# 04_SHIELD_SLOT_B.net
KiCad netlist of a schematic drawn in Altium Designer
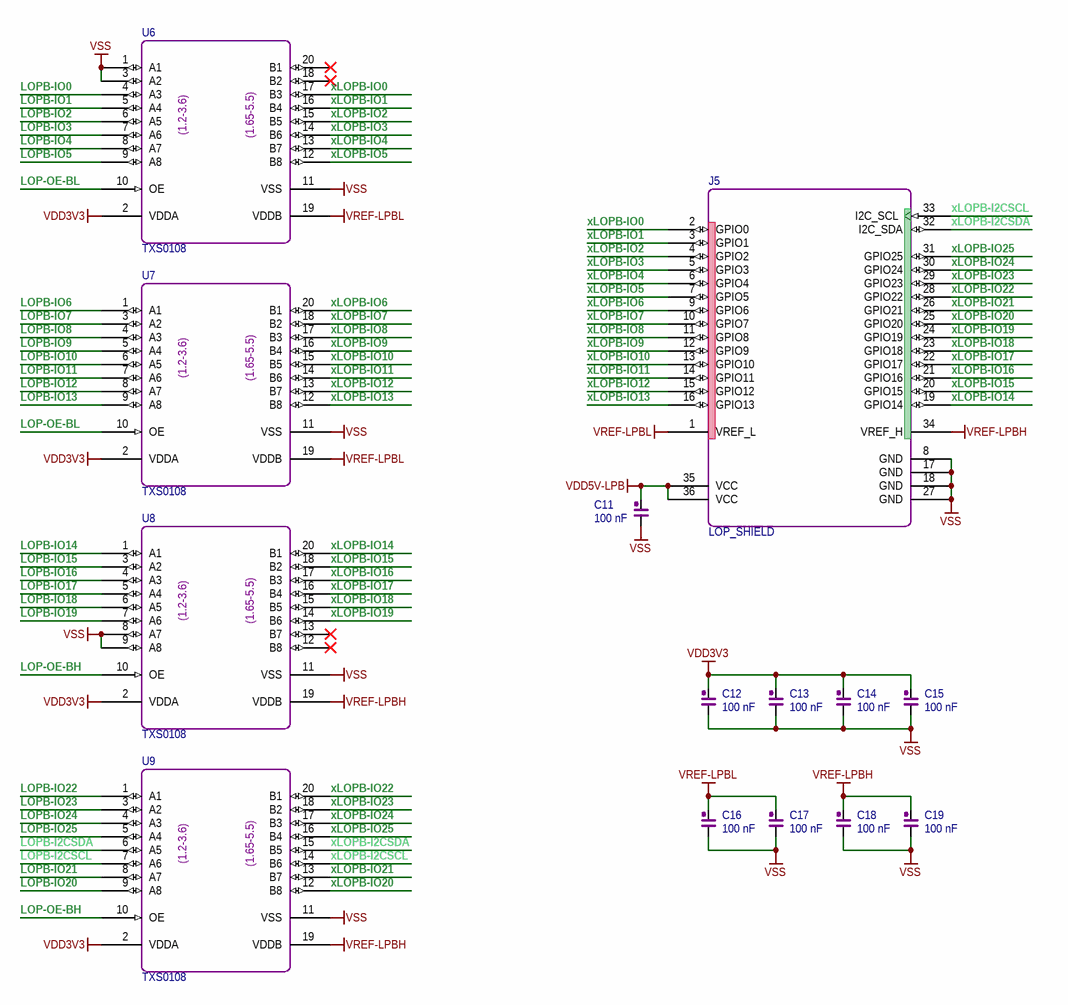
[diagram p0: 04_SHIELD_SLOT_B.SchDoc]

(export (version "E")
  (design (tool "Eeschema 10.0.6"))
  (components
    (comp (ref "C11")
      (value "100 nF")
      (footprint "0603A1")
      (description "Normal Capacitor")
      (fields
        (field (name "PARTNUMBER") "0")
        (field (name "PUBLISHER") "Cowin")
        (field (name "DESIGNER") "shyul")
      )
      (libsource (lib "Basc_1_Passive") (part "CAP"))
    )
    (comp (ref "C12")
      (value "100 nF")
      (footprint "0603A1")
      (description "Normal Capacitor")
      (fields
        (field (name "PARTNUMBER") "0")
        (field (name "PUBLISHER") "Cowin")
        (field (name "DESIGNER") "shyul")
      )
      (libsource (lib "Basc_1_Passive") (part "CAP"))
    )
    (comp (ref "C13")
      (value "100 nF")
      (footprint "0603A1")
      (description "Normal Capacitor")
      (fields
        (field (name "PARTNUMBER") "0")
        (field (name "PUBLISHER") "Cowin")
        (field (name "DESIGNER") "shyul")
      )
      (libsource (lib "Basc_1_Passive") (part "CAP"))
    )
    (comp (ref "C14")
      (value "100 nF")
      (footprint "0603A1")
      (description "Normal Capacitor")
      (fields
        (field (name "PARTNUMBER") "0")
        (field (name "PUBLISHER") "Cowin")
        (field (name "DESIGNER") "shyul")
      )
      (libsource (lib "Basc_1_Passive") (part "CAP"))
    )
    (comp (ref "C15")
      (value "100 nF")
      (footprint "0603A1")
      (description "Normal Capacitor")
      (fields
        (field (name "PARTNUMBER") "0")
        (field (name "PUBLISHER") "Cowin")
        (field (name "DESIGNER") "shyul")
      )
      (libsource (lib "Basc_1_Passive") (part "CAP"))
    )
    (comp (ref "C16")
      (value "100 nF")
      (footprint "0603A1")
      (description "Normal Capacitor")
      (fields
        (field (name "PARTNUMBER") "0")
        (field (name "PUBLISHER") "Cowin")
        (field (name "DESIGNER") "shyul")
      )
      (libsource (lib "Basc_1_Passive") (part "CAP"))
    )
    (comp (ref "C17")
      (value "100 nF")
      (footprint "0603A1")
      (description "Normal Capacitor")
      (fields
        (field (name "PARTNUMBER") "0")
        (field (name "PUBLISHER") "Cowin")
        (field (name "DESIGNER") "shyul")
      )
      (libsource (lib "Basc_1_Passive") (part "CAP"))
    )
    (comp (ref "C18")
      (value "100 nF")
      (footprint "0603A1")
      (description "Normal Capacitor")
      (fields
        (field (name "PARTNUMBER") "0")
        (field (name "PUBLISHER") "Cowin")
        (field (name "DESIGNER") "shyul")
      )
      (libsource (lib "Basc_1_Passive") (part "CAP"))
    )
    (comp (ref "C19")
      (value "100 nF")
      (footprint "0603A1")
      (description "Normal Capacitor")
      (fields
        (field (name "PARTNUMBER") "0")
        (field (name "PUBLISHER") "Cowin")
        (field (name "DESIGNER") "shyul")
      )
      (libsource (lib "Basc_1_Passive") (part "CAP"))
    )
    (comp (ref "J5")
      (value "LOP_SHIELD")
      (footprint "LOP_SHIELD")
      (description "Lophilo Shield Module Slot")
      (fields (field (name "PUBLISHER") "Cowin") (field (name "DESIGNER") "shyul"))
      (libsource (lib "PCB_LDB-U01") (part "LOP_SHIELD"))
    )
    (comp (ref "U6")
      (value "TXS0108")
      (footprint "TSSOP-20")
      (description "8-bit Translator")
      (fields (field (name "DESIGNER") "shyul") (field (name "PUBLISHER") "Cowin"))
      (libsource (lib "IC_01_Logic") (part "TXS0108"))
    )
    (comp (ref "U7")
      (value "TXS0108")
      (footprint "TSSOP-20")
      (description "8-bit Translator")
      (fields (field (name "DESIGNER") "shyul") (field (name "PUBLISHER") "Cowin"))
      (libsource (lib "IC_01_Logic") (part "TXS0108"))
    )
    (comp (ref "U8")
      (value "TXS0108")
      (footprint "TSSOP-20")
      (description "8-bit Translator")
      (fields (field (name "DESIGNER") "shyul") (field (name "PUBLISHER") "Cowin"))
      (libsource (lib "IC_01_Logic") (part "TXS0108"))
    )
    (comp (ref "U9")
      (value "TXS0108")
      (footprint "TSSOP-20")
      (description "8-bit Translator")
      (fields (field (name "DESIGNER") "shyul") (field (name "PUBLISHER") "Cowin"))
      (libsource (lib "IC_01_Logic") (part "TXS0108"))
    )
  )
  (nets
    (net (code "1") (name "/LOP-OE-BH") (class "Default")
      (node (ref "U8") (pin "10") (pinfunction "OE_10") (pintype "input"))
      (node (ref "U9") (pin "10") (pinfunction "OE_10") (pintype "input"))
    )
    (net (code "2") (name "/LOP-OE-BL") (class "Default")
      (node (ref "U6") (pin "10") (pinfunction "OE_10") (pintype "input"))
      (node (ref "U7") (pin "10") (pinfunction "OE_10") (pintype "input"))
    )
    (net (code "3") (name "/LOPB-I2CSCL") (class "Default")
      (node (ref "U9") (pin "7") (pinfunction "A6_7") (pintype "bidirectional"))
    )
    (net (code "4") (name "/LOPB-I2CSDA") (class "Default")
      (node (ref "U9") (pin "6") (pinfunction "A5_6") (pintype "bidirectional"))
    )
    (net (code "5") (name "/LOPB-IO0") (class "Default")
      (node (ref "U6") (pin "4") (pinfunction "A3_4") (pintype "bidirectional"))
    )
    (net (code "6") (name "/LOPB-IO1") (class "Default")
      (node (ref "U6") (pin "5") (pinfunction "A4_5") (pintype "bidirectional"))
    )
    (net (code "7") (name "/LOPB-IO2") (class "Default")
      (node (ref "U6") (pin "6") (pinfunction "A5_6") (pintype "bidirectional"))
    )
    (net (code "8") (name "/LOPB-IO3") (class "Default")
      (node (ref "U6") (pin "7") (pinfunction "A6_7") (pintype "bidirectional"))
    )
    (net (code "9") (name "/LOPB-IO4") (class "Default")
      (node (ref "U6") (pin "8") (pinfunction "A7_8") (pintype "bidirectional"))
    )
    (net (code "10") (name "/LOPB-IO5") (class "Default")
      (node (ref "U6") (pin "9") (pinfunction "A8_9") (pintype "bidirectional"))
    )
    (net (code "11") (name "/LOPB-IO6") (class "Default")
      (node (ref "U7") (pin "1") (pinfunction "A1_1") (pintype "bidirectional"))
    )
    (net (code "12") (name "/LOPB-IO7") (class "Default")
      (node (ref "U7") (pin "3") (pinfunction "A2_3") (pintype "bidirectional"))
    )
    (net (code "13") (name "/LOPB-IO8") (class "Default")
      (node (ref "U7") (pin "4") (pinfunction "A3_4") (pintype "bidirectional"))
    )
    (net (code "14") (name "/LOPB-IO9") (class "Default")
      (node (ref "U7") (pin "5") (pinfunction "A4_5") (pintype "bidirectional"))
    )
    (net (code "15") (name "/LOPB-IO10") (class "Default")
      (node (ref "U7") (pin "6") (pinfunction "A5_6") (pintype "bidirectional"))
    )
    (net (code "16") (name "/LOPB-IO11") (class "Default")
      (node (ref "U7") (pin "7") (pinfunction "A6_7") (pintype "bidirectional"))
    )
    (net (code "17") (name "/LOPB-IO12") (class "Default")
      (node (ref "U7") (pin "8") (pinfunction "A7_8") (pintype "bidirectional"))
    )
    (net (code "18") (name "/LOPB-IO13") (class "Default")
      (node (ref "U7") (pin "9") (pinfunction "A8_9") (pintype "bidirectional"))
    )
    (net (code "19") (name "/LOPB-IO14") (class "Default")
      (node (ref "U8") (pin "1") (pinfunction "A1_1") (pintype "bidirectional"))
    )
    (net (code "20") (name "/LOPB-IO15") (class "Default")
      (node (ref "U8") (pin "3") (pinfunction "A2_3") (pintype "bidirectional"))
    )
    (net (code "21") (name "/LOPB-IO16") (class "Default")
      (node (ref "U8") (pin "4") (pinfunction "A3_4") (pintype "bidirectional"))
    )
    (net (code "22") (name "/LOPB-IO17") (class "Default")
      (node (ref "U8") (pin "5") (pinfunction "A4_5") (pintype "bidirectional"))
    )
    (net (code "23") (name "/LOPB-IO18") (class "Default")
      (node (ref "U8") (pin "6") (pinfunction "A5_6") (pintype "bidirectional"))
    )
    (net (code "24") (name "/LOPB-IO19") (class "Default")
      (node (ref "U8") (pin "7") (pinfunction "A6_7") (pintype "bidirectional"))
    )
    (net (code "25") (name "/LOPB-IO20") (class "Default")
      (node (ref "U9") (pin "9") (pinfunction "A8_9") (pintype "bidirectional"))
    )
    (net (code "26") (name "/LOPB-IO21") (class "Default")
      (node (ref "U9") (pin "8") (pinfunction "A7_8") (pintype "bidirectional"))
    )
    (net (code "27") (name "/LOPB-IO22") (class "Default")
      (node (ref "U9") (pin "1") (pinfunction "A1_1") (pintype "bidirectional"))
    )
    (net (code "28") (name "/LOPB-IO23") (class "Default")
      (node (ref "U9") (pin "3") (pinfunction "A2_3") (pintype "bidirectional"))
    )
    (net (code "29") (name "/LOPB-IO24") (class "Default")
      (node (ref "U9") (pin "4") (pinfunction "A3_4") (pintype "bidirectional"))
    )
    (net (code "30") (name "/LOPB-IO25") (class "Default")
      (node (ref "U9") (pin "5") (pinfunction "A4_5") (pintype "bidirectional"))
    )
    (net (code "31") (name "/xLOPB-I2CSCL") (class "Default")
      (node (ref "J5") (pin "33") (pinfunction "I2C_SCL_33") (pintype "input"))
      (node (ref "U9") (pin "14") (pinfunction "B6_14") (pintype "bidirectional"))
    )
    (net (code "32") (name "/xLOPB-I2CSDA") (class "Default")
      (node (ref "J5") (pin "32") (pinfunction "I2C_SDA_32") (pintype "bidirectional"))
      (node (ref "U9") (pin "15") (pinfunction "B5_15") (pintype "bidirectional"))
    )
    (net (code "33") (name "/xLOPB-IO0") (class "Default")
      (node (ref "J5") (pin "2") (pinfunction "GPIO0_2") (pintype "bidirectional"))
      (node (ref "U6") (pin "17") (pinfunction "B3_17") (pintype "bidirectional"))
    )
    (net (code "34") (name "/xLOPB-IO1") (class "Default")
      (node (ref "J5") (pin "3") (pinfunction "GPIO1_3") (pintype "bidirectional"))
      (node (ref "U6") (pin "16") (pinfunction "B4_16") (pintype "bidirectional"))
    )
    (net (code "35") (name "/xLOPB-IO2") (class "Default")
      (node (ref "J5") (pin "4") (pinfunction "GPIO2_4") (pintype "bidirectional"))
      (node (ref "U6") (pin "15") (pinfunction "B5_15") (pintype "bidirectional"))
    )
    (net (code "36") (name "/xLOPB-IO3") (class "Default")
      (node (ref "J5") (pin "5") (pinfunction "GPIO3_5") (pintype "bidirectional"))
      (node (ref "U6") (pin "14") (pinfunction "B6_14") (pintype "bidirectional"))
    )
    (net (code "37") (name "/xLOPB-IO4") (class "Default")
      (node (ref "J5") (pin "6") (pinfunction "GPIO4_6") (pintype "bidirectional"))
      (node (ref "U6") (pin "13") (pinfunction "B7_13") (pintype "bidirectional"))
    )
    (net (code "38") (name "/xLOPB-IO5") (class "Default")
      (node (ref "J5") (pin "7") (pinfunction "GPIO5_7") (pintype "bidirectional"))
      (node (ref "U6") (pin "12") (pinfunction "B8_12") (pintype "bidirectional"))
    )
    (net (code "39") (name "/xLOPB-IO6") (class "Default")
      (node (ref "J5") (pin "9") (pinfunction "GPIO6_9") (pintype "bidirectional"))
      (node (ref "U7") (pin "20") (pinfunction "B1_20") (pintype "bidirectional"))
    )
    (net (code "40") (name "/xLOPB-IO7") (class "Default")
      (node (ref "J5") (pin "10") (pinfunction "GPIO7_10") (pintype "bidirectional"))
      (node (ref "U7") (pin "18") (pinfunction "B2_18") (pintype "bidirectional"))
    )
    (net (code "41") (name "/xLOPB-IO8") (class "Default")
      (node (ref "J5") (pin "11") (pinfunction "GPIO8_11") (pintype "bidirectional"))
      (node (ref "U7") (pin "17") (pinfunction "B3_17") (pintype "bidirectional"))
    )
    (net (code "42") (name "/xLOPB-IO9") (class "Default")
      (node (ref "J5") (pin "12") (pinfunction "GPIO9_12") (pintype "bidirectional"))
      (node (ref "U7") (pin "16") (pinfunction "B4_16") (pintype "bidirectional"))
    )
    (net (code "43") (name "/xLOPB-IO10") (class "Default")
      (node (ref "J5") (pin "13") (pinfunction "GPIO10_13") (pintype "bidirectional"))
      (node (ref "U7") (pin "15") (pinfunction "B5_15") (pintype "bidirectional"))
    )
    (net (code "44") (name "/xLOPB-IO11") (class "Default")
      (node (ref "J5") (pin "14") (pinfunction "GPIO11_14") (pintype "bidirectional"))
      (node (ref "U7") (pin "14") (pinfunction "B6_14") (pintype "bidirectional"))
    )
    (net (code "45") (name "/xLOPB-IO12") (class "Default")
      (node (ref "J5") (pin "15") (pinfunction "GPIO12_15") (pintype "bidirectional"))
      (node (ref "U7") (pin "13") (pinfunction "B7_13") (pintype "bidirectional"))
    )
    (net (code "46") (name "/xLOPB-IO13") (class "Default")
      (node (ref "J5") (pin "16") (pinfunction "GPIO13_16") (pintype "bidirectional"))
      (node (ref "U7") (pin "12") (pinfunction "B8_12") (pintype "bidirectional"))
    )
    (net (code "47") (name "/xLOPB-IO14") (class "Default")
      (node (ref "J5") (pin "19") (pinfunction "GPIO14_19") (pintype "bidirectional"))
      (node (ref "U8") (pin "20") (pinfunction "B1_20") (pintype "bidirectional"))
    )
    (net (code "48") (name "/xLOPB-IO15") (class "Default")
      (node (ref "J5") (pin "20") (pinfunction "GPIO15_20") (pintype "bidirectional"))
      (node (ref "U8") (pin "18") (pinfunction "B2_18") (pintype "bidirectional"))
    )
    (net (code "49") (name "/xLOPB-IO16") (class "Default")
      (node (ref "J5") (pin "21") (pinfunction "GPIO16_21") (pintype "bidirectional"))
      (node (ref "U8") (pin "17") (pinfunction "B3_17") (pintype "bidirectional"))
    )
    (net (code "50") (name "/xLOPB-IO17") (class "Default")
      (node (ref "J5") (pin "22") (pinfunction "GPIO17_22") (pintype "bidirectional"))
      (node (ref "U8") (pin "16") (pinfunction "B4_16") (pintype "bidirectional"))
    )
    (net (code "51") (name "/xLOPB-IO18") (class "Default")
      (node (ref "J5") (pin "23") (pinfunction "GPIO18_23") (pintype "bidirectional"))
      (node (ref "U8") (pin "15") (pinfunction "B5_15") (pintype "bidirectional"))
    )
    (net (code "52") (name "/xLOPB-IO19") (class "Default")
      (node (ref "J5") (pin "24") (pinfunction "GPIO19_24") (pintype "bidirectional"))
      (node (ref "U8") (pin "14") (pinfunction "B6_14") (pintype "bidirectional"))
    )
    (net (code "53") (name "/xLOPB-IO20") (class "Default")
      (node (ref "J5") (pin "25") (pinfunction "GPIO20_25") (pintype "bidirectional"))
      (node (ref "U9") (pin "12") (pinfunction "B8_12") (pintype "bidirectional"))
    )
    (net (code "54") (name "/xLOPB-IO21") (class "Default")
      (node (ref "J5") (pin "26") (pinfunction "GPIO21_26") (pintype "bidirectional"))
      (node (ref "U9") (pin "13") (pinfunction "B7_13") (pintype "bidirectional"))
    )
    (net (code "55") (name "/xLOPB-IO22") (class "Default")
      (node (ref "J5") (pin "28") (pinfunction "GPIO22_28") (pintype "bidirectional"))
      (node (ref "U9") (pin "20") (pinfunction "B1_20") (pintype "bidirectional"))
    )
    (net (code "56") (name "/xLOPB-IO23") (class "Default")
      (node (ref "J5") (pin "29") (pinfunction "GPIO23_29") (pintype "bidirectional"))
      (node (ref "U9") (pin "18") (pinfunction "B2_18") (pintype "bidirectional"))
    )
    (net (code "57") (name "/xLOPB-IO24") (class "Default")
      (node (ref "J5") (pin "30") (pinfunction "GPIO24_30") (pintype "bidirectional"))
      (node (ref "U9") (pin "17") (pinfunction "B3_17") (pintype "bidirectional"))
    )
    (net (code "58") (name "/xLOPB-IO25") (class "Default")
      (node (ref "J5") (pin "31") (pinfunction "GPIO25_31") (pintype "bidirectional"))
      (node (ref "U9") (pin "16") (pinfunction "B4_16") (pintype "bidirectional"))
    )
    (net (code "59") (name "VDD3V3") (class "Default")
      (node (ref "C12") (pin "2") (pinfunction "2_2") (pintype "passive"))
      (node (ref "C13") (pin "2") (pinfunction "2_2") (pintype "passive"))
      (node (ref "C14") (pin "2") (pinfunction "2_2") (pintype "passive"))
      (node (ref "C15") (pin "2") (pinfunction "2_2") (pintype "passive"))
      (node (ref "U6") (pin "2") (pinfunction "VDDA_2") (pintype "power_in"))
      (node (ref "U7") (pin "2") (pinfunction "VDDA_2") (pintype "power_in"))
      (node (ref "U8") (pin "2") (pinfunction "VDDA_2") (pintype "power_in"))
      (node (ref "U9") (pin "2") (pinfunction "VDDA_2") (pintype "power_in"))
    )
    (net (code "60") (name "VDD5V-LPB") (class "Default")
      (node (ref "C11") (pin "2") (pinfunction "2_2") (pintype "passive"))
      (node (ref "J5") (pin "35") (pinfunction "VCC_35") (pintype "passive"))
      (node (ref "J5") (pin "36") (pinfunction "VCC_36") (pintype "passive"))
    )
    (net (code "61") (name "VREF-LPBH") (class "Default")
      (node (ref "C18") (pin "2") (pinfunction "2_2") (pintype "passive"))
      (node (ref "C19") (pin "2") (pinfunction "2_2") (pintype "passive"))
      (node (ref "J5") (pin "34") (pinfunction "VREF_H_34") (pintype "power_in"))
      (node (ref "U8") (pin "19") (pinfunction "VDDB_19") (pintype "power_in"))
      (node (ref "U9") (pin "19") (pinfunction "VDDB_19") (pintype "power_in"))
    )
    (net (code "62") (name "VREF-LPBL") (class "Default")
      (node (ref "C16") (pin "2") (pinfunction "2_2") (pintype "passive"))
      (node (ref "C17") (pin "2") (pinfunction "2_2") (pintype "passive"))
      (node (ref "J5") (pin "1") (pinfunction "VREF_L_1") (pintype "power_in"))
      (node (ref "U6") (pin "19") (pinfunction "VDDB_19") (pintype "power_in"))
      (node (ref "U7") (pin "19") (pinfunction "VDDB_19") (pintype "power_in"))
    )
    (net (code "63") (name "VSS") (class "Default")
      (node (ref "C11") (pin "1") (pinfunction "1_1") (pintype "passive"))
      (node (ref "C12") (pin "1") (pinfunction "1_1") (pintype "passive"))
      (node (ref "C13") (pin "1") (pinfunction "1_1") (pintype "passive"))
      (node (ref "C14") (pin "1") (pinfunction "1_1") (pintype "passive"))
      (node (ref "C15") (pin "1") (pinfunction "1_1") (pintype "passive"))
      (node (ref "C16") (pin "1") (pinfunction "1_1") (pintype "passive"))
      (node (ref "C17") (pin "1") (pinfunction "1_1") (pintype "passive"))
      (node (ref "C18") (pin "1") (pinfunction "1_1") (pintype "passive"))
      (node (ref "C19") (pin "1") (pinfunction "1_1") (pintype "passive"))
      (node (ref "J5") (pin "17") (pinfunction "GND_17") (pintype "passive"))
      (node (ref "J5") (pin "18") (pinfunction "GND_18") (pintype "passive"))
      (node (ref "J5") (pin "27") (pinfunction "GND_27") (pintype "passive"))
      (node (ref "J5") (pin "8") (pinfunction "GND_8") (pintype "passive"))
      (node (ref "U6") (pin "1") (pinfunction "A1_1") (pintype "bidirectional"))
      (node (ref "U6") (pin "11") (pinfunction "VSS_11") (pintype "passive"))
      (node (ref "U6") (pin "3") (pinfunction "A2_3") (pintype "bidirectional"))
      (node (ref "U7") (pin "11") (pinfunction "VSS_11") (pintype "passive"))
      (node (ref "U8") (pin "11") (pinfunction "VSS_11") (pintype "passive"))
      (node (ref "U8") (pin "8") (pinfunction "A7_8") (pintype "bidirectional"))
      (node (ref "U8") (pin "9") (pinfunction "A8_9") (pintype "bidirectional"))
      (node (ref "U9") (pin "11") (pinfunction "VSS_11") (pintype "passive"))
    )
    (net (code "64") (name "unconnected-(U6-B1-Pad20)") (class "Default")
      (node (ref "U6") (pin "20") (pinfunction "B1_20") (pintype "bidirectional+no_connect"))
    )
    (net (code "65") (name "unconnected-(U6-B2-Pad18)") (class "Default")
      (node (ref "U6") (pin "18") (pinfunction "B2_18") (pintype "bidirectional+no_connect"))
    )
    (net (code "66") (name "unconnected-(U8-B7-Pad13)") (class "Default")
      (node (ref "U8") (pin "13") (pinfunction "B7_13") (pintype "bidirectional+no_connect"))
    )
    (net (code "67") (name "unconnected-(U8-B8-Pad12)") (class "Default")
      (node (ref "U8") (pin "12") (pinfunction "B8_12") (pintype "bidirectional+no_connect"))
    )
  )
)
